# RFswitch.net
KiCad netlist of a schematic drawn in Altium Designer
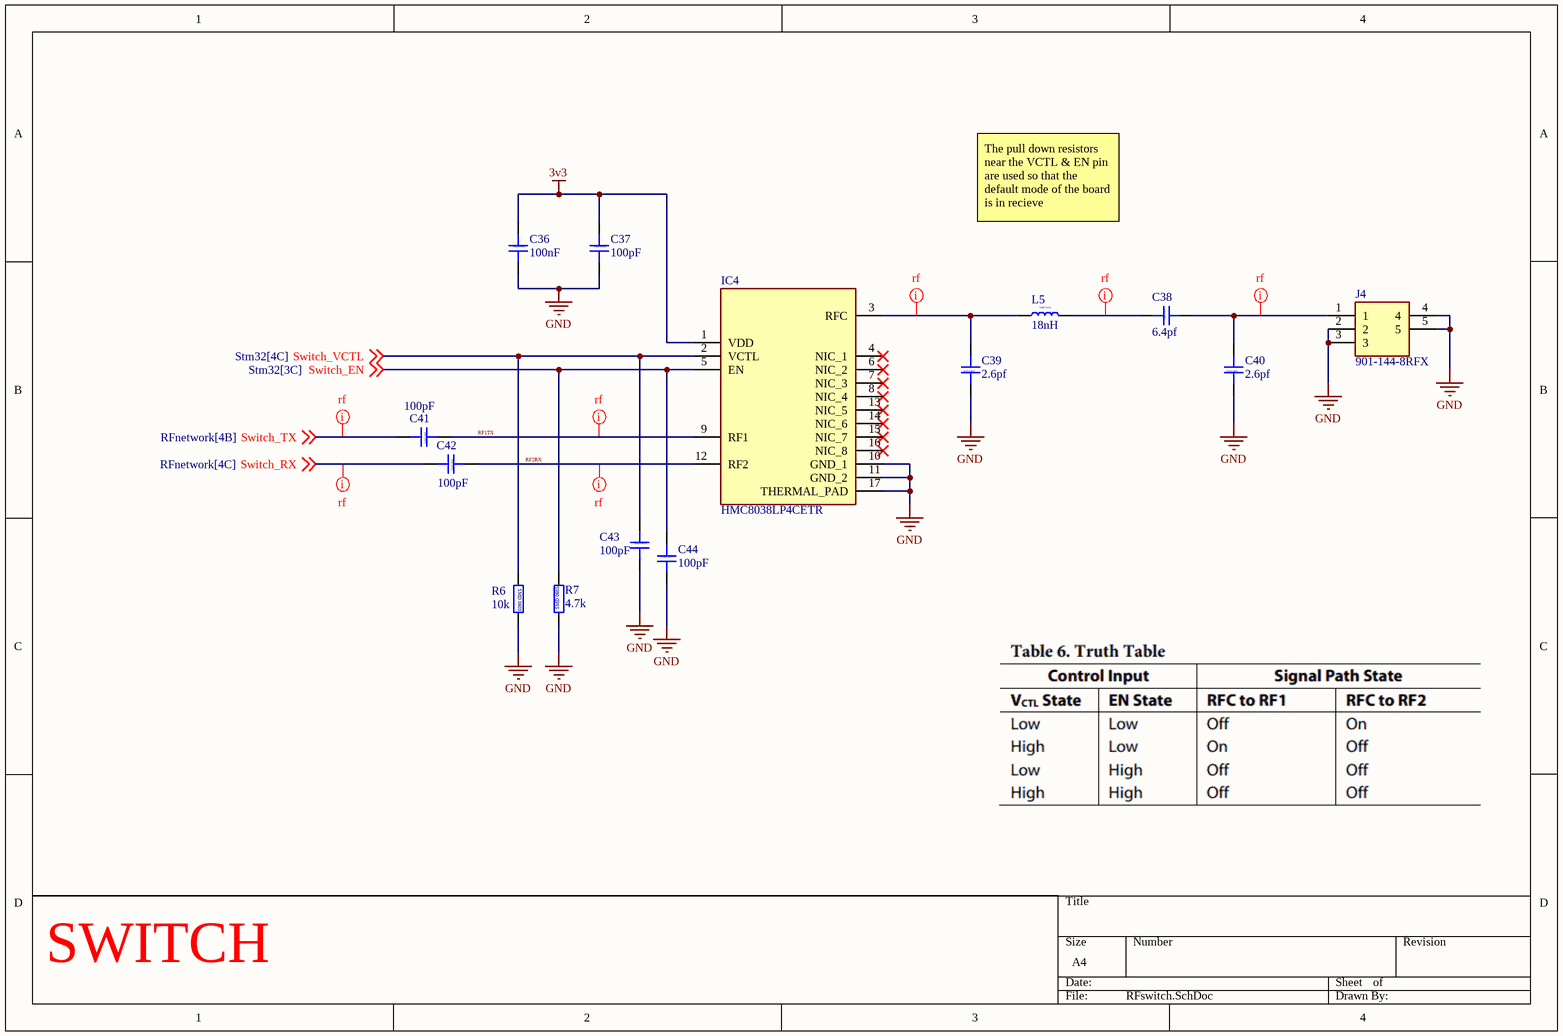
[diagram p0: RFswitch.SchDoc]

(export (version "E")
  (design (tool "Eeschema 10.0.6"))
  (components
    (comp (ref "C36")
      (value "100nF")
      (footprint "CAP_0603")
      (description "Capacitor SMD 0603 RATED")
      (libsource (lib "STeRG-Passives-Standard") (part "Capacitor-SMD-0603"))
    )
    (comp (ref "C37")
      (value "100pF")
      (footprint "CAP_0603")
      (description "Capacitor SMD 0603 RATED")
      (libsource (lib "STeRG-Passives-Standard") (part "Capacitor-SMD-0603"))
    )
    (comp (ref "C38")
      (value "6.4pf")
      (footprint "CAP_0402")
      (description "Capacitor SMD 0402 RATED")
      (libsource (lib "STeRG-Passives-Standard") (part "Capacitor-SMD-0402"))
    )
    (comp (ref "C39")
      (value "2.6pf")
      (footprint "CAP_0402")
      (description "Capacitor SMD 0402 RATED")
      (libsource (lib "STeRG-Passives-Standard") (part "Capacitor-SMD-0402"))
    )
    (comp (ref "C40")
      (value "2.6pf")
      (footprint "CAP_0402")
      (description "Capacitor SMD 0402 RATED")
      (libsource (lib "STeRG-Passives-Standard") (part "Capacitor-SMD-0402"))
    )
    (comp (ref "C41")
      (value "100pF")
      (footprint "CAP_0603")
      (description "Capacitor SMD 0603 RATED")
      (libsource (lib "STeRG-Passives-Standard") (part "Capacitor-SMD-0603"))
    )
    (comp (ref "C42")
      (value "100pF")
      (footprint "CAP_0603")
      (description "Capacitor SMD 0603 RATED")
      (libsource (lib "STeRG-Passives-Standard") (part "Capacitor-SMD-0603"))
    )
    (comp (ref "C43")
      (value "100pF")
      (footprint "CAP_0603")
      (description "Capacitor SMD 0603 RATED")
      (libsource (lib "STeRG-Passives-Standard") (part "Capacitor-SMD-0603"))
    )
    (comp (ref "C44")
      (value "100pF")
      (footprint "CAP_0603")
      (description "Capacitor SMD 0603 RATED")
      (libsource (lib "STeRG-Passives-Standard") (part "Capacitor-SMD-0603"))
    )
    (comp (ref "IC4")
      (value "HMC8038LP4CETR")
      (footprint "SamacSys:QFN65P400X400X90-17N-D")
      (description "Integrated Circuit")
      (fields (field (name "MOUSER PART NUMBER") "584-HMC8038LP4CETR"))
      (libsource (lib "SamacSys") (part "HMC8038LP4CETR"))
    )
    (comp (ref "J4")
      (value "901-144-8RFX")
      (footprint "9011448RFX")
      (description "AMPHENOL RF - 901-144-8RFX - RF / Coaxial Connector")
      (fields (field (name "MOUSER PART NUMBER") "523-901-144-8RFX"))
      (libsource (lib "SamacSys") (part "901-144-8RFX"))
    )
    (comp (ref "L5")
      (value "18nH")
      (footprint "IND_0402")
      (description "Inductor SMD 0402")
      (libsource (lib "STeRG-Passives-Standard") (part "Inductor-SMD-RF-0402"))
    )
    (comp (ref "R6")
      (value "10k")
      (footprint "RES_0603")
      (description "Resistor SMD 0603 RATED")
      (libsource (lib "STeRG-Passives-Standard") (part "Resistor-SMD-0603"))
    )
    (comp (ref "R7")
      (value "4.7k")
      (footprint "RES_0603")
      (description "Resistor SMD 0603 RATED")
      (libsource (lib "STeRG-Passives-Standard") (part "Resistor-SMD-0603"))
    )
  )
  (nets
    (net (code "1") (name "/RF1TX") (class "Default")
      (node (ref "C41") (pin "1") (pinfunction "1_1") (pintype "passive"))
      (node (ref "IC4") (pin "9") (pinfunction "RF1_9") (pintype "passive"))
    )
    (net (code "2") (name "/RF2RX") (class "Default")
      (node (ref "C42") (pin "1") (pinfunction "1_1") (pintype "passive"))
      (node (ref "IC4") (pin "12") (pinfunction "RF2_12") (pintype "passive"))
    )
    (net (code "3") (name "3v3") (class "Default")
      (node (ref "C36") (pin "1") (pinfunction "1_1") (pintype "passive"))
      (node (ref "C37") (pin "1") (pinfunction "1_1") (pintype "passive"))
      (node (ref "IC4") (pin "1") (pinfunction "VDD_1") (pintype "passive"))
    )
    (net (code "4") (name "GND") (class "Default")
      (node (ref "C36") (pin "2") (pinfunction "2_2") (pintype "passive"))
      (node (ref "C37") (pin "2") (pinfunction "2_2") (pintype "passive"))
      (node (ref "C39") (pin "1") (pinfunction "1_1") (pintype "passive"))
      (node (ref "C40") (pin "1") (pinfunction "1_1") (pintype "passive"))
      (node (ref "C43") (pin "2") (pinfunction "2_2") (pintype "passive"))
      (node (ref "C44") (pin "2") (pinfunction "2_2") (pintype "passive"))
      (node (ref "IC4") (pin "10") (pinfunction "GND_1_10") (pintype "passive"))
      (node (ref "IC4") (pin "11") (pinfunction "GND_2_11") (pintype "passive"))
      (node (ref "IC4") (pin "17") (pinfunction "THERMAL_PAD_17") (pintype "passive"))
      (node (ref "J4") (pin "2") (pinfunction "2_2") (pintype "passive"))
      (node (ref "J4") (pin "3") (pinfunction "3_3") (pintype "passive"))
      (node (ref "J4") (pin "4") (pinfunction "4_4") (pintype "passive"))
      (node (ref "J4") (pin "5") (pinfunction "5_5") (pintype "passive"))
      (node (ref "R6") (pin "2") (pinfunction "2_2") (pintype "passive"))
      (node (ref "R7") (pin "1") (pinfunction "1_1") (pintype "passive"))
    )
    (net (code "5") (name "Net-(C38-Pad1)") (class "Default")
      (node (ref "C38") (pin "1") (pinfunction "1_1") (pintype "passive"))
      (node (ref "L5") (pin "2") (pinfunction "2_2") (pintype "passive"))
    )
    (net (code "6") (name "Net-(C38-Pad2)") (class "Default")
      (node (ref "C38") (pin "2") (pinfunction "2_2") (pintype "passive"))
      (node (ref "C40") (pin "2") (pinfunction "2_2") (pintype "passive"))
      (node (ref "J4") (pin "1") (pinfunction "1_1") (pintype "passive"))
    )
    (net (code "7") (name "Net-(IC4-RFC)") (class "Default")
      (node (ref "C39") (pin "2") (pinfunction "2_2") (pintype "passive"))
      (node (ref "IC4") (pin "3") (pinfunction "RFC_3") (pintype "passive"))
      (node (ref "L5") (pin "1") (pinfunction "1_1") (pintype "passive"))
    )
    (net (code "8") (name "Switch_EN") (class "Default")
      (node (ref "C44") (pin "1") (pinfunction "1_1") (pintype "passive"))
      (node (ref "IC4") (pin "5") (pinfunction "EN_5") (pintype "passive"))
      (node (ref "R7") (pin "2") (pinfunction "2_2") (pintype "passive"))
    )
    (net (code "9") (name "Switch_RX") (class "Default")
      (node (ref "C42") (pin "2") (pinfunction "2_2") (pintype "passive"))
    )
    (net (code "10") (name "Switch_TX") (class "Default")
      (node (ref "C41") (pin "2") (pinfunction "2_2") (pintype "passive"))
    )
    (net (code "11") (name "Switch_VCTL") (class "Default")
      (node (ref "C43") (pin "1") (pinfunction "1_1") (pintype "passive"))
      (node (ref "IC4") (pin "2") (pinfunction "VCTL_2") (pintype "passive"))
      (node (ref "R6") (pin "1") (pinfunction "1_1") (pintype "passive"))
    )
    (net (code "12") (name "unconnected-(IC4-NIC_1-Pad4)") (class "Default")
      (node (ref "IC4") (pin "4") (pinfunction "NIC_1_4") (pintype "passive+no_connect"))
    )
    (net (code "13") (name "unconnected-(IC4-NIC_2-Pad6)") (class "Default")
      (node (ref "IC4") (pin "6") (pinfunction "NIC_2_6") (pintype "passive+no_connect"))
    )
    (net (code "14") (name "unconnected-(IC4-NIC_3-Pad7)") (class "Default")
      (node (ref "IC4") (pin "7") (pinfunction "NIC_3_7") (pintype "passive+no_connect"))
    )
    (net (code "15") (name "unconnected-(IC4-NIC_4-Pad8)") (class "Default")
      (node (ref "IC4") (pin "8") (pinfunction "NIC_4_8") (pintype "passive+no_connect"))
    )
    (net (code "16") (name "unconnected-(IC4-NIC_5-Pad13)") (class "Default")
      (node (ref "IC4") (pin "13") (pinfunction "NIC_5_13") (pintype "passive+no_connect"))
    )
    (net (code "17") (name "unconnected-(IC4-NIC_6-Pad14)") (class "Default")
      (node (ref "IC4") (pin "14") (pinfunction "NIC_6_14") (pintype "passive+no_connect"))
    )
    (net (code "18") (name "unconnected-(IC4-NIC_7-Pad15)") (class "Default")
      (node (ref "IC4") (pin "15") (pinfunction "NIC_7_15") (pintype "passive+no_connect"))
    )
    (net (code "19") (name "unconnected-(IC4-NIC_8-Pad16)") (class "Default")
      (node (ref "IC4") (pin "16") (pinfunction "NIC_8_16") (pintype "passive+no_connect"))
    )
  )
)
